# USB_HUB_4_Port.net
KiCad netlist of a schematic drawn in Altium Designer
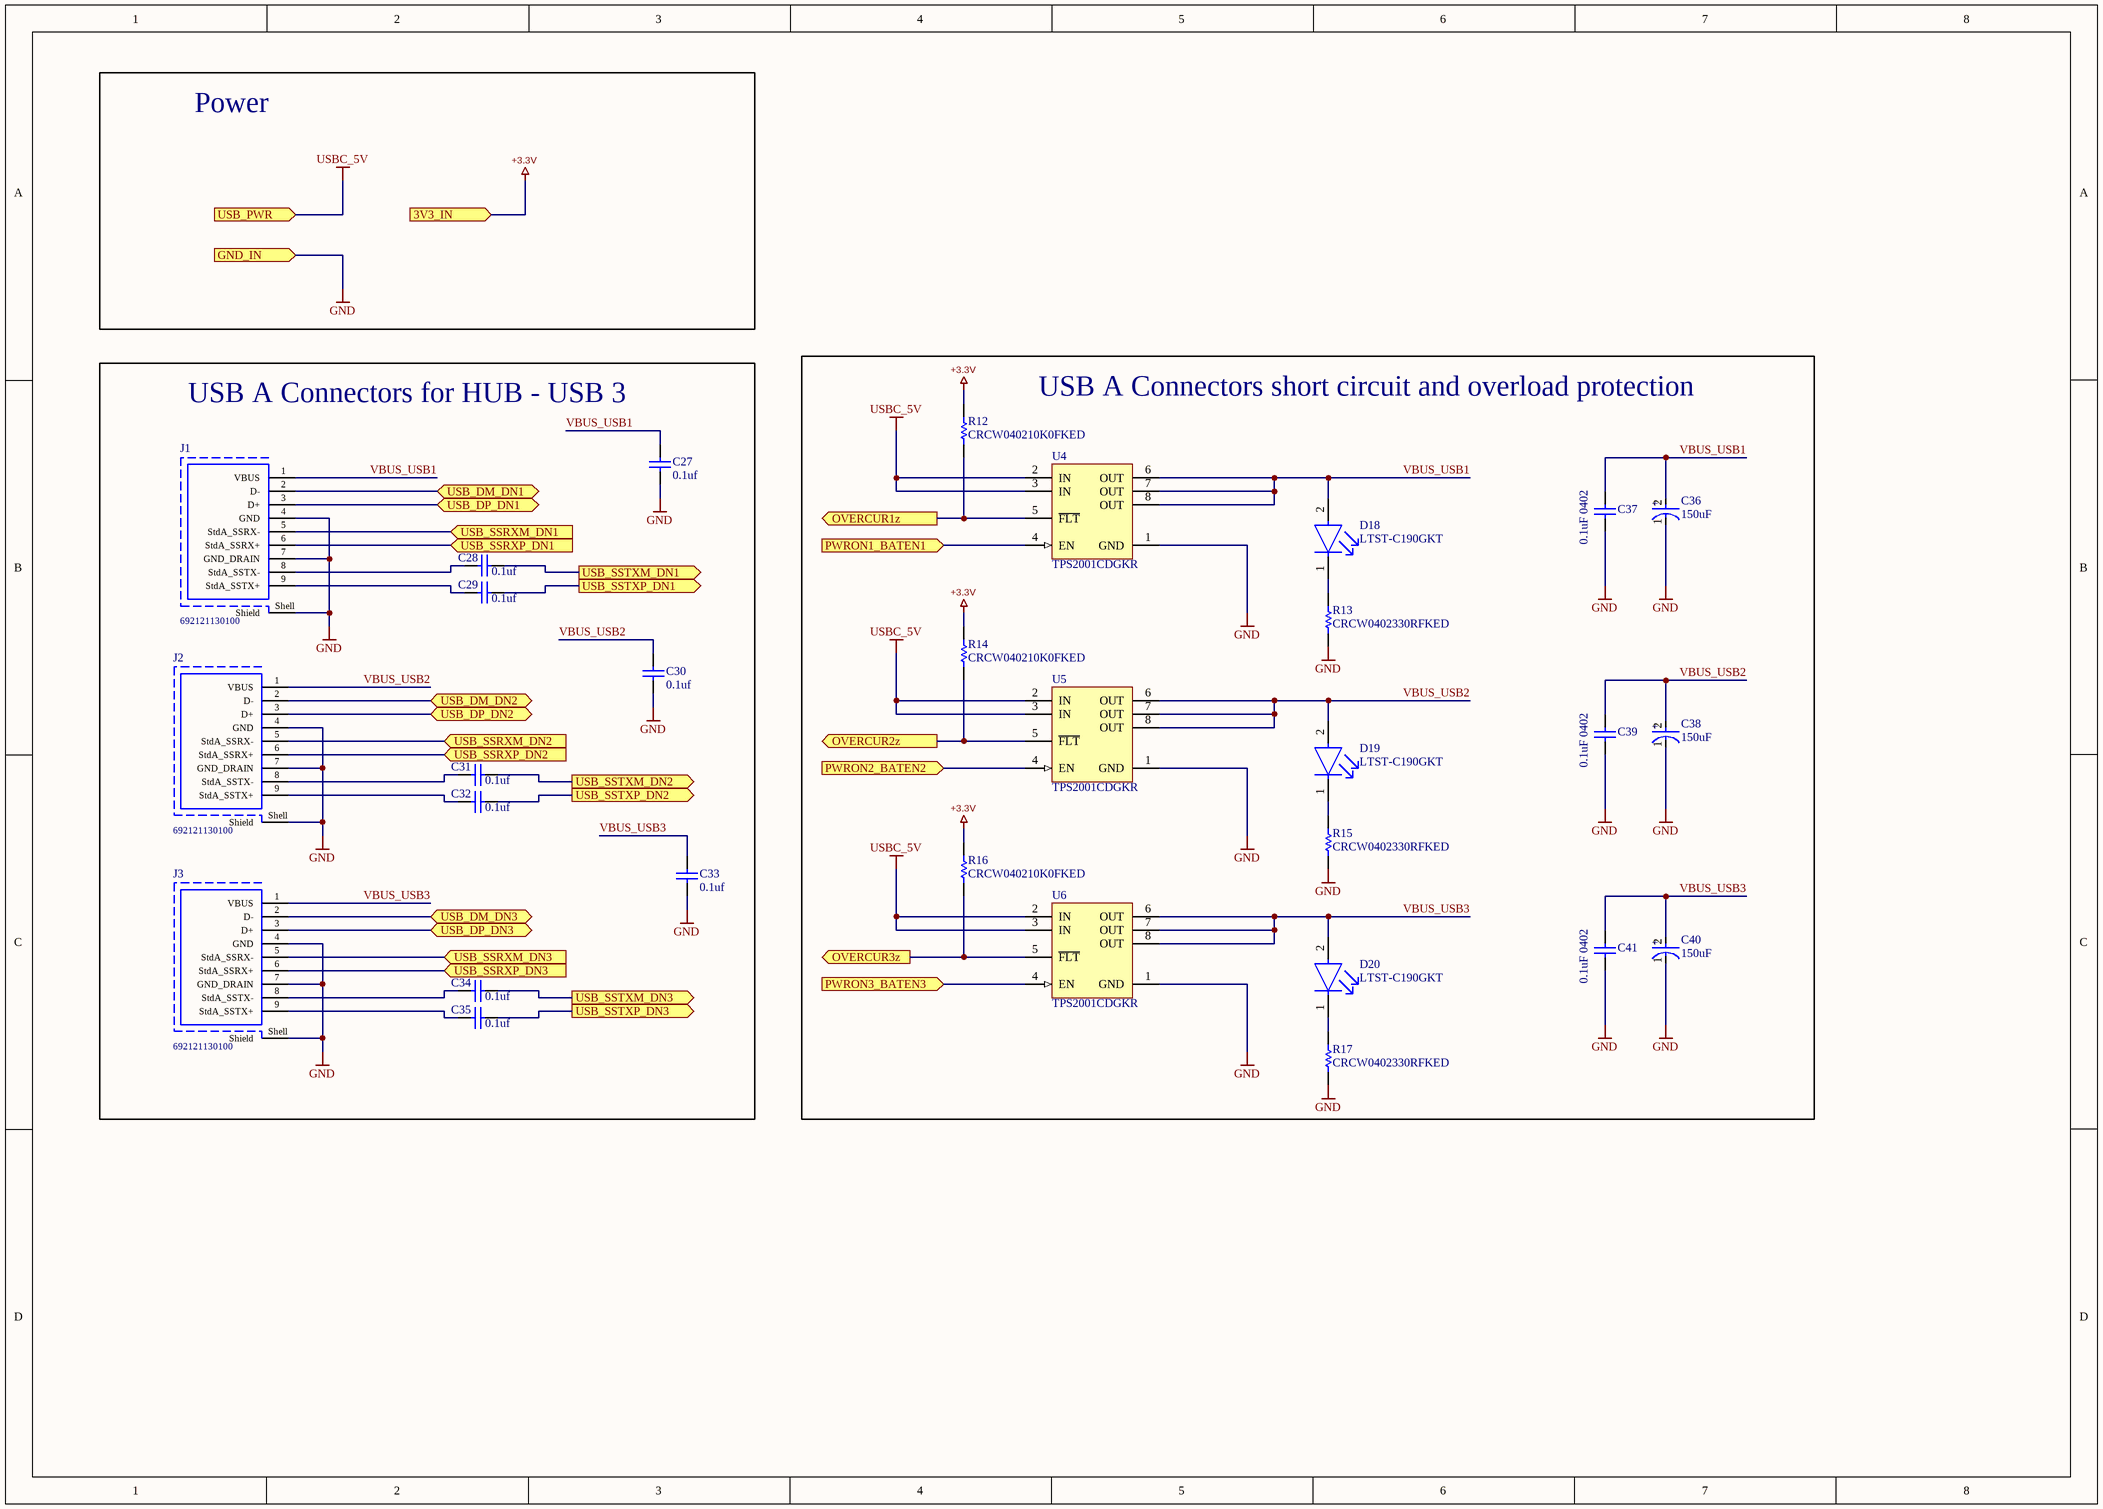
[diagram p0: USB_HUB_4 Port.SchDoc]

(export (version "E")
  (design (tool "Eeschema 10.0.6"))
  (components
    (comp (ref "C27")
      (value "0.1uf")
      (footprint "CAPC1005X55X30ML05T10")
      (fields (field (name "MANUFACTURER") "Kemet") (field (name "PART NUMBER") "C0402C104J4RACTU"))
      (libsource (lib "Altium Content Vault") (part "CAP"))
    )
    (comp (ref "C28")
      (value "0.1uf")
      (footprint "CAPC1005X55X30ML05T10")
      (fields (field (name "MANUFACTURER") "Kemet") (field (name "PART NUMBER") "C0402C104J4RACTU"))
      (libsource (lib "Altium Content Vault") (part "CAP"))
    )
    (comp (ref "C29")
      (value "0.1uf")
      (footprint "CAPC1005X55X30ML05T10")
      (fields (field (name "MANUFACTURER") "Kemet") (field (name "PART NUMBER") "C0402C104J4RACTU"))
      (libsource (lib "Altium Content Vault") (part "CAP"))
    )
    (comp (ref "C30")
      (value "0.1uf")
      (footprint "CAPC1005X55X30ML05T10")
      (fields (field (name "MANUFACTURER") "Kemet") (field (name "PART NUMBER") "C0402C104J4RACTU"))
      (libsource (lib "Altium Content Vault") (part "CAP"))
    )
    (comp (ref "C31")
      (value "0.1uf")
      (footprint "CAPC1005X55X30ML05T10")
      (fields (field (name "MANUFACTURER") "Kemet") (field (name "PART NUMBER") "C0402C104J4RACTU"))
      (libsource (lib "Altium Content Vault") (part "CAP"))
    )
    (comp (ref "C32")
      (value "0.1uf")
      (footprint "CAPC1005X55X30ML05T10")
      (fields (field (name "MANUFACTURER") "Kemet") (field (name "PART NUMBER") "C0402C104J4RACTU"))
      (libsource (lib "Altium Content Vault") (part "CAP"))
    )
    (comp (ref "C33")
      (value "0.1uf")
      (footprint "CAPC1005X55X30ML05T10")
      (fields (field (name "MANUFACTURER") "Kemet") (field (name "PART NUMBER") "C0402C104J4RACTU"))
      (libsource (lib "Altium Content Vault") (part "CAP"))
    )
    (comp (ref "C34")
      (value "0.1uf")
      (footprint "CAPC1005X55X30ML05T10")
      (fields (field (name "MANUFACTURER") "Kemet") (field (name "PART NUMBER") "C0402C104J4RACTU"))
      (libsource (lib "Altium Content Vault") (part "CAP"))
    )
    (comp (ref "C35")
      (value "0.1uf")
      (footprint "CAPC1005X55X30ML05T10")
      (fields (field (name "MANUFACTURER") "Kemet") (field (name "PART NUMBER") "C0402C104J4RACTU"))
      (libsource (lib "Altium Content Vault") (part "CAP"))
    )
    (comp (ref "C36")
      (value "150uF")
      (footprint "FP-SVPEB6-MFG")
      (description "CAP ALUM POLY 150UF 20% 6.3V SMD")
      (fields (field (name "TOLERANCE") "20%") (field (name "VOLTAGE") "6.3V"))
      (libsource (lib "Altium Content Vault") (part "203bc49f2ac43e59fd269a8c329ed05"))
    )
    (comp (ref "C37")
      (value "0.1uF 0402")
      (footprint "CAPC1005X55X30ML05T10")
      (fields (field (name "MANUFACTURER") "Kemet") (field (name "PART NUMBER") "C0402C104J4RACTU"))
      (libsource (lib "Altium Content Vault") (part "CAP"))
    )
    (comp (ref "C38")
      (value "150uF")
      (footprint "FP-SVPEB6-MFG")
      (description "CAP ALUM POLY 150UF 20% 6.3V SMD")
      (fields (field (name "TOLERANCE") "20%") (field (name "VOLTAGE") "6.3V"))
      (libsource (lib "Altium Content Vault") (part "203bc49f2ac43e59fd269a8c329ed05"))
    )
    (comp (ref "C39")
      (value "0.1uF 0402")
      (footprint "CAPC1005X55X30ML05T10")
      (fields (field (name "MANUFACTURER") "Kemet") (field (name "PART NUMBER") "C0402C104J4RACTU"))
      (libsource (lib "Altium Content Vault") (part "CAP"))
    )
    (comp (ref "C40")
      (value "150uF")
      (footprint "FP-SVPEB6-MFG")
      (description "CAP ALUM POLY 150UF 20% 6.3V SMD")
      (fields (field (name "TOLERANCE") "20%") (field (name "VOLTAGE") "6.3V"))
      (libsource (lib "Altium Content Vault") (part "203bc49f2ac43e59fd269a8c329ed05"))
    )
    (comp (ref "C41")
      (value "0.1uF 0402")
      (footprint "CAPC1005X55X30ML05T10")
      (fields (field (name "MANUFACTURER") "Kemet") (field (name "PART NUMBER") "C0402C104J4RACTU"))
      (libsource (lib "Altium Content Vault") (part "CAP"))
    )
    (comp (ref "D18")
      (value "LTST-C190GKT")
      (footprint "FP-LTST-C190GKT-MFG")
      (description "LED GREEN CLEAR CHIP SMD")
      (fields (field (name "VOLTAGE") "2V"))
      (libsource (lib "Altium Content Vault") (part "8706943c75ba83719d021d2fdc84c58"))
    )
    (comp (ref "D19")
      (value "LTST-C190GKT")
      (footprint "FP-LTST-C190GKT-MFG")
      (description "LED GREEN CLEAR CHIP SMD")
      (fields (field (name "VOLTAGE") "2V"))
      (libsource (lib "Altium Content Vault") (part "8706943c75ba83719d021d2fdc84c58"))
    )
    (comp (ref "D20")
      (value "LTST-C190GKT")
      (footprint "FP-LTST-C190GKT-MFG")
      (description "LED GREEN CLEAR CHIP SMD")
      (fields (field (name "VOLTAGE") "2V"))
      (libsource (lib "Altium Content Vault") (part "8706943c75ba83719d021d2fdc84c58"))
    )
    (comp (ref "J1")
      (value "692121130100")
      (footprint "692121130100")
      (description "USB 3.0 Type A Receptacle WR-COM, Reverse Horizontal, SMT / THT, with Clips, with 0.14 mm Offset")
      (fields (field (name "MANUFACTURER") "Wurth Elektronik") (field (name "PUBLISHER") "WurthElektronik"))
      (libsource (lib "Altium Content Vault") (part "WE-USB-9-1SHLD"))
    )
    (comp (ref "J2")
      (value "692121130100")
      (footprint "692121130100")
      (description "USB 3.0 Type A Receptacle WR-COM, Reverse Horizontal, SMT / THT, with Clips, with 0.14 mm Offset")
      (fields (field (name "MANUFACTURER") "Wurth Elektronik") (field (name "PUBLISHER") "WurthElektronik"))
      (libsource (lib "Altium Content Vault") (part "WE-USB-9-1SHLD"))
    )
    (comp (ref "J3")
      (value "692121130100")
      (footprint "692121130100")
      (description "USB 3.0 Type A Receptacle WR-COM, Reverse Horizontal, SMT / THT, with Clips, with 0.14 mm Offset")
      (fields (field (name "MANUFACTURER") "Wurth Elektronik") (field (name "PUBLISHER") "WurthElektronik"))
      (libsource (lib "Altium Content Vault") (part "WE-USB-9-1SHLD"))
    )
    (comp (ref "R12")
      (value "CRCW040210K0FKED")
      (footprint "RESC1005X40X25NL05T05")
      (fields (field (name "MANUFACTURER") "Vishay Dale"))
      (libsource (lib "Altium Content Vault") (part "RES"))
    )
    (comp (ref "R13")
      (value "CRCW0402330RFKED")
      (footprint "RESC1005X40X25NL05T05")
      (fields (field (name "MANUFACTURER") "Vishay Dale"))
      (libsource (lib "Altium Content Vault") (part "RES"))
    )
    (comp (ref "R14")
      (value "CRCW040210K0FKED")
      (footprint "RESC1005X40X25NL05T05")
      (fields (field (name "MANUFACTURER") "Vishay Dale"))
      (libsource (lib "Altium Content Vault") (part "RES"))
    )
    (comp (ref "R15")
      (value "CRCW0402330RFKED")
      (footprint "RESC1005X40X25NL05T05")
      (fields (field (name "MANUFACTURER") "Vishay Dale"))
      (libsource (lib "Altium Content Vault") (part "RES"))
    )
    (comp (ref "R16")
      (value "CRCW040210K0FKED")
      (footprint "RESC1005X40X25NL05T05")
      (fields (field (name "MANUFACTURER") "Vishay Dale"))
      (libsource (lib "Altium Content Vault") (part "RES"))
    )
    (comp (ref "R17")
      (value "CRCW0402330RFKED")
      (footprint "RESC1005X40X25NL05T05")
      (fields (field (name "MANUFACTURER") "Vishay Dale"))
      (libsource (lib "Altium Content Vault") (part "RES"))
    )
    (comp (ref "U4")
      (value "TPS2001CDGKR")
      (footprint "DGK0008A_L")
      (fields (field (name "MANUFACTURER") "Texas Instruments"))
      (libsource (lib "Altium Content Vault") (part "TI-TPS2001CDGK8"))
    )
    (comp (ref "U5")
      (value "TPS2001CDGKR")
      (footprint "DGK0008A_L")
      (fields (field (name "MANUFACTURER") "Texas Instruments"))
      (libsource (lib "Altium Content Vault") (part "TI-TPS2001CDGK8"))
    )
    (comp (ref "U6")
      (value "TPS2001CDGKR")
      (footprint "DGK0008A_L")
      (fields (field (name "MANUFACTURER") "Texas Instruments"))
      (libsource (lib "Altium Content Vault") (part "TI-TPS2001CDGK8"))
    )
  )
  (nets
    (net (code "1") (name "+3.3V") (class "Default")
      (node (ref "R12") (pin "2") (pinfunction "2_2") (pintype "passive"))
      (node (ref "R14") (pin "2") (pinfunction "2_2") (pintype "passive"))
      (node (ref "R16") (pin "2") (pinfunction "2_2") (pintype "passive"))
    )
    (net (code "2") (name "/OVERCUR1z") (class "Default")
      (node (ref "R12") (pin "1") (pinfunction "1_1") (pintype "passive"))
      (node (ref "U4") (pin "5") (pinfunction "~{FLT}_5") (pintype "tri_state"))
    )
    (net (code "3") (name "/OVERCUR2z") (class "Default")
      (node (ref "R14") (pin "1") (pinfunction "1_1") (pintype "passive"))
      (node (ref "U5") (pin "5") (pinfunction "~{FLT}_5") (pintype "tri_state"))
    )
    (net (code "4") (name "/OVERCUR3z") (class "Default")
      (node (ref "R16") (pin "1") (pinfunction "1_1") (pintype "passive"))
      (node (ref "U6") (pin "5") (pinfunction "~{FLT}_5") (pintype "tri_state"))
    )
    (net (code "5") (name "/PWRON1_BATEN1") (class "Default")
      (node (ref "U4") (pin "4") (pinfunction "EN_4") (pintype "input"))
    )
    (net (code "6") (name "/PWRON2_BATEN2") (class "Default")
      (node (ref "U5") (pin "4") (pinfunction "EN_4") (pintype "input"))
    )
    (net (code "7") (name "/PWRON3_BATEN3") (class "Default")
      (node (ref "U6") (pin "4") (pinfunction "EN_4") (pintype "input"))
    )
    (net (code "8") (name "/USB_DM_DN1") (class "Default")
      (node (ref "J1") (pin "2") (pinfunction "D-_2") (pintype "passive"))
    )
    (net (code "9") (name "/USB_DM_DN2") (class "Default")
      (node (ref "J2") (pin "2") (pinfunction "D-_2") (pintype "passive"))
    )
    (net (code "10") (name "/USB_DM_DN3") (class "Default")
      (node (ref "J3") (pin "2") (pinfunction "D-_2") (pintype "passive"))
    )
    (net (code "11") (name "/USB_DP_DN1") (class "Default")
      (node (ref "J1") (pin "3") (pinfunction "D+_3") (pintype "passive"))
    )
    (net (code "12") (name "/USB_DP_DN2") (class "Default")
      (node (ref "J2") (pin "3") (pinfunction "D+_3") (pintype "passive"))
    )
    (net (code "13") (name "/USB_DP_DN3") (class "Default")
      (node (ref "J3") (pin "3") (pinfunction "D+_3") (pintype "passive"))
    )
    (net (code "14") (name "/USB_SSRXM_DN1") (class "Default")
      (node (ref "J1") (pin "5") (pinfunction "StdA_SSRX-_5") (pintype "passive"))
    )
    (net (code "15") (name "/USB_SSRXM_DN2") (class "Default")
      (node (ref "J2") (pin "5") (pinfunction "StdA_SSRX-_5") (pintype "passive"))
    )
    (net (code "16") (name "/USB_SSRXM_DN3") (class "Default")
      (node (ref "J3") (pin "5") (pinfunction "StdA_SSRX-_5") (pintype "passive"))
    )
    (net (code "17") (name "/USB_SSRXP_DN1") (class "Default")
      (node (ref "J1") (pin "6") (pinfunction "StdA_SSRX+_6") (pintype "passive"))
    )
    (net (code "18") (name "/USB_SSRXP_DN2") (class "Default")
      (node (ref "J2") (pin "6") (pinfunction "StdA_SSRX+_6") (pintype "passive"))
    )
    (net (code "19") (name "/USB_SSRXP_DN3") (class "Default")
      (node (ref "J3") (pin "6") (pinfunction "StdA_SSRX+_6") (pintype "passive"))
    )
    (net (code "20") (name "/USB_SSTXM_DN1") (class "Default")
      (node (ref "C28") (pin "2") (pinfunction "2_2") (pintype "passive"))
    )
    (net (code "21") (name "/USB_SSTXM_DN2") (class "Default")
      (node (ref "C31") (pin "2") (pinfunction "2_2") (pintype "passive"))
    )
    (net (code "22") (name "/USB_SSTXM_DN3") (class "Default")
      (node (ref "C34") (pin "2") (pinfunction "2_2") (pintype "passive"))
    )
    (net (code "23") (name "/USB_SSTXP_DN1") (class "Default")
      (node (ref "C29") (pin "2") (pinfunction "2_2") (pintype "passive"))
    )
    (net (code "24") (name "/USB_SSTXP_DN2") (class "Default")
      (node (ref "C32") (pin "2") (pinfunction "2_2") (pintype "passive"))
    )
    (net (code "25") (name "/USB_SSTXP_DN3") (class "Default")
      (node (ref "C35") (pin "2") (pinfunction "2_2") (pintype "passive"))
    )
    (net (code "26") (name "/VBUS_USB1") (class "Default")
      (node (ref "C27") (pin "2") (pinfunction "2_2") (pintype "passive"))
      (node (ref "C36") (pin "2") (pinfunction "A_2") (pintype "passive"))
      (node (ref "C37") (pin "2") (pinfunction "2_2") (pintype "passive"))
      (node (ref "D18") (pin "2") (pinfunction "A_2") (pintype "passive"))
      (node (ref "J1") (pin "1") (pinfunction "VBUS_1") (pintype "passive"))
      (node (ref "U4") (pin "6") (pinfunction "OUT_6") (pintype "power_in"))
      (node (ref "U4") (pin "7") (pinfunction "OUT_7") (pintype "power_in"))
      (node (ref "U4") (pin "8") (pinfunction "OUT_8") (pintype "power_in"))
    )
    (net (code "27") (name "/VBUS_USB2") (class "Default")
      (node (ref "C30") (pin "2") (pinfunction "2_2") (pintype "passive"))
      (node (ref "C38") (pin "2") (pinfunction "A_2") (pintype "passive"))
      (node (ref "C39") (pin "2") (pinfunction "2_2") (pintype "passive"))
      (node (ref "D19") (pin "2") (pinfunction "A_2") (pintype "passive"))
      (node (ref "J2") (pin "1") (pinfunction "VBUS_1") (pintype "passive"))
      (node (ref "U5") (pin "6") (pinfunction "OUT_6") (pintype "power_in"))
      (node (ref "U5") (pin "7") (pinfunction "OUT_7") (pintype "power_in"))
      (node (ref "U5") (pin "8") (pinfunction "OUT_8") (pintype "power_in"))
    )
    (net (code "28") (name "/VBUS_USB3") (class "Default")
      (node (ref "C33") (pin "2") (pinfunction "2_2") (pintype "passive"))
      (node (ref "C40") (pin "2") (pinfunction "A_2") (pintype "passive"))
      (node (ref "C41") (pin "2") (pinfunction "2_2") (pintype "passive"))
      (node (ref "D20") (pin "2") (pinfunction "A_2") (pintype "passive"))
      (node (ref "J3") (pin "1") (pinfunction "VBUS_1") (pintype "passive"))
      (node (ref "U6") (pin "6") (pinfunction "OUT_6") (pintype "power_in"))
      (node (ref "U6") (pin "7") (pinfunction "OUT_7") (pintype "power_in"))
      (node (ref "U6") (pin "8") (pinfunction "OUT_8") (pintype "power_in"))
    )
    (net (code "29") (name "GND") (class "Default")
      (node (ref "C27") (pin "1") (pinfunction "1_1") (pintype "passive"))
      (node (ref "C30") (pin "1") (pinfunction "1_1") (pintype "passive"))
      (node (ref "C33") (pin "1") (pinfunction "1_1") (pintype "passive"))
      (node (ref "C36") (pin "1") (pinfunction "C_1") (pintype "passive"))
      (node (ref "C37") (pin "1") (pinfunction "1_1") (pintype "passive"))
      (node (ref "C38") (pin "1") (pinfunction "C_1") (pintype "passive"))
      (node (ref "C39") (pin "1") (pinfunction "1_1") (pintype "passive"))
      (node (ref "C40") (pin "1") (pinfunction "C_1") (pintype "passive"))
      (node (ref "C41") (pin "1") (pinfunction "1_1") (pintype "passive"))
      (node (ref "J1") (pin "4") (pinfunction "GND_4") (pintype "passive"))
      (node (ref "J1") (pin "7") (pinfunction "GND_DRAIN_7") (pintype "passive"))
      (node (ref "J1") (pin "Shell") (pinfunction "Shield_Shell") (pintype "passive"))
      (node (ref "J2") (pin "4") (pinfunction "GND_4") (pintype "passive"))
      (node (ref "J2") (pin "7") (pinfunction "GND_DRAIN_7") (pintype "passive"))
      (node (ref "J2") (pin "Shell") (pinfunction "Shield_Shell") (pintype "passive"))
      (node (ref "J3") (pin "4") (pinfunction "GND_4") (pintype "passive"))
      (node (ref "J3") (pin "7") (pinfunction "GND_DRAIN_7") (pintype "passive"))
      (node (ref "J3") (pin "Shell") (pinfunction "Shield_Shell") (pintype "passive"))
      (node (ref "R13") (pin "1") (pinfunction "1_1") (pintype "passive"))
      (node (ref "R15") (pin "1") (pinfunction "1_1") (pintype "passive"))
      (node (ref "R17") (pin "1") (pinfunction "1_1") (pintype "passive"))
      (node (ref "U4") (pin "1") (pinfunction "GND_1") (pintype "power_in"))
      (node (ref "U5") (pin "1") (pinfunction "GND_1") (pintype "power_in"))
      (node (ref "U6") (pin "1") (pinfunction "GND_1") (pintype "power_in"))
    )
    (net (code "30") (name "Net-(D18-C)") (class "Default")
      (node (ref "D18") (pin "1") (pinfunction "C_1") (pintype "passive"))
      (node (ref "R13") (pin "2") (pinfunction "2_2") (pintype "passive"))
    )
    (net (code "31") (name "Net-(D19-C)") (class "Default")
      (node (ref "D19") (pin "1") (pinfunction "C_1") (pintype "passive"))
      (node (ref "R15") (pin "2") (pinfunction "2_2") (pintype "passive"))
    )
    (net (code "32") (name "Net-(D20-C)") (class "Default")
      (node (ref "D20") (pin "1") (pinfunction "C_1") (pintype "passive"))
      (node (ref "R17") (pin "2") (pinfunction "2_2") (pintype "passive"))
    )
    (net (code "33") (name "Net-(J1-StdA_SSTX+)") (class "Default")
      (node (ref "C29") (pin "1") (pinfunction "1_1") (pintype "passive"))
      (node (ref "J1") (pin "9") (pinfunction "StdA_SSTX+_9") (pintype "passive"))
    )
    (net (code "34") (name "Net-(J1-StdA_SSTX-)") (class "Default")
      (node (ref "C28") (pin "1") (pinfunction "1_1") (pintype "passive"))
      (node (ref "J1") (pin "8") (pinfunction "StdA_SSTX-_8") (pintype "passive"))
    )
    (net (code "35") (name "Net-(J2-StdA_SSTX+)") (class "Default")
      (node (ref "C32") (pin "1") (pinfunction "1_1") (pintype "passive"))
      (node (ref "J2") (pin "9") (pinfunction "StdA_SSTX+_9") (pintype "passive"))
    )
    (net (code "36") (name "Net-(J2-StdA_SSTX-)") (class "Default")
      (node (ref "C31") (pin "1") (pinfunction "1_1") (pintype "passive"))
      (node (ref "J2") (pin "8") (pinfunction "StdA_SSTX-_8") (pintype "passive"))
    )
    (net (code "37") (name "Net-(J3-StdA_SSTX+)") (class "Default")
      (node (ref "C35") (pin "1") (pinfunction "1_1") (pintype "passive"))
      (node (ref "J3") (pin "9") (pinfunction "StdA_SSTX+_9") (pintype "passive"))
    )
    (net (code "38") (name "Net-(J3-StdA_SSTX-)") (class "Default")
      (node (ref "C34") (pin "1") (pinfunction "1_1") (pintype "passive"))
      (node (ref "J3") (pin "8") (pinfunction "StdA_SSTX-_8") (pintype "passive"))
    )
    (net (code "39") (name "USBC_5V") (class "Default")
      (node (ref "U4") (pin "2") (pinfunction "IN_2") (pintype "power_in"))
      (node (ref "U4") (pin "3") (pinfunction "IN_3") (pintype "power_in"))
      (node (ref "U5") (pin "2") (pinfunction "IN_2") (pintype "power_in"))
      (node (ref "U5") (pin "3") (pinfunction "IN_3") (pintype "power_in"))
      (node (ref "U6") (pin "2") (pinfunction "IN_2") (pintype "power_in"))
      (node (ref "U6") (pin "3") (pinfunction "IN_3") (pintype "power_in"))
    )
  )
)
